# Emoji_Board.net
KiCad netlist of a schematic drawn in EAGLE
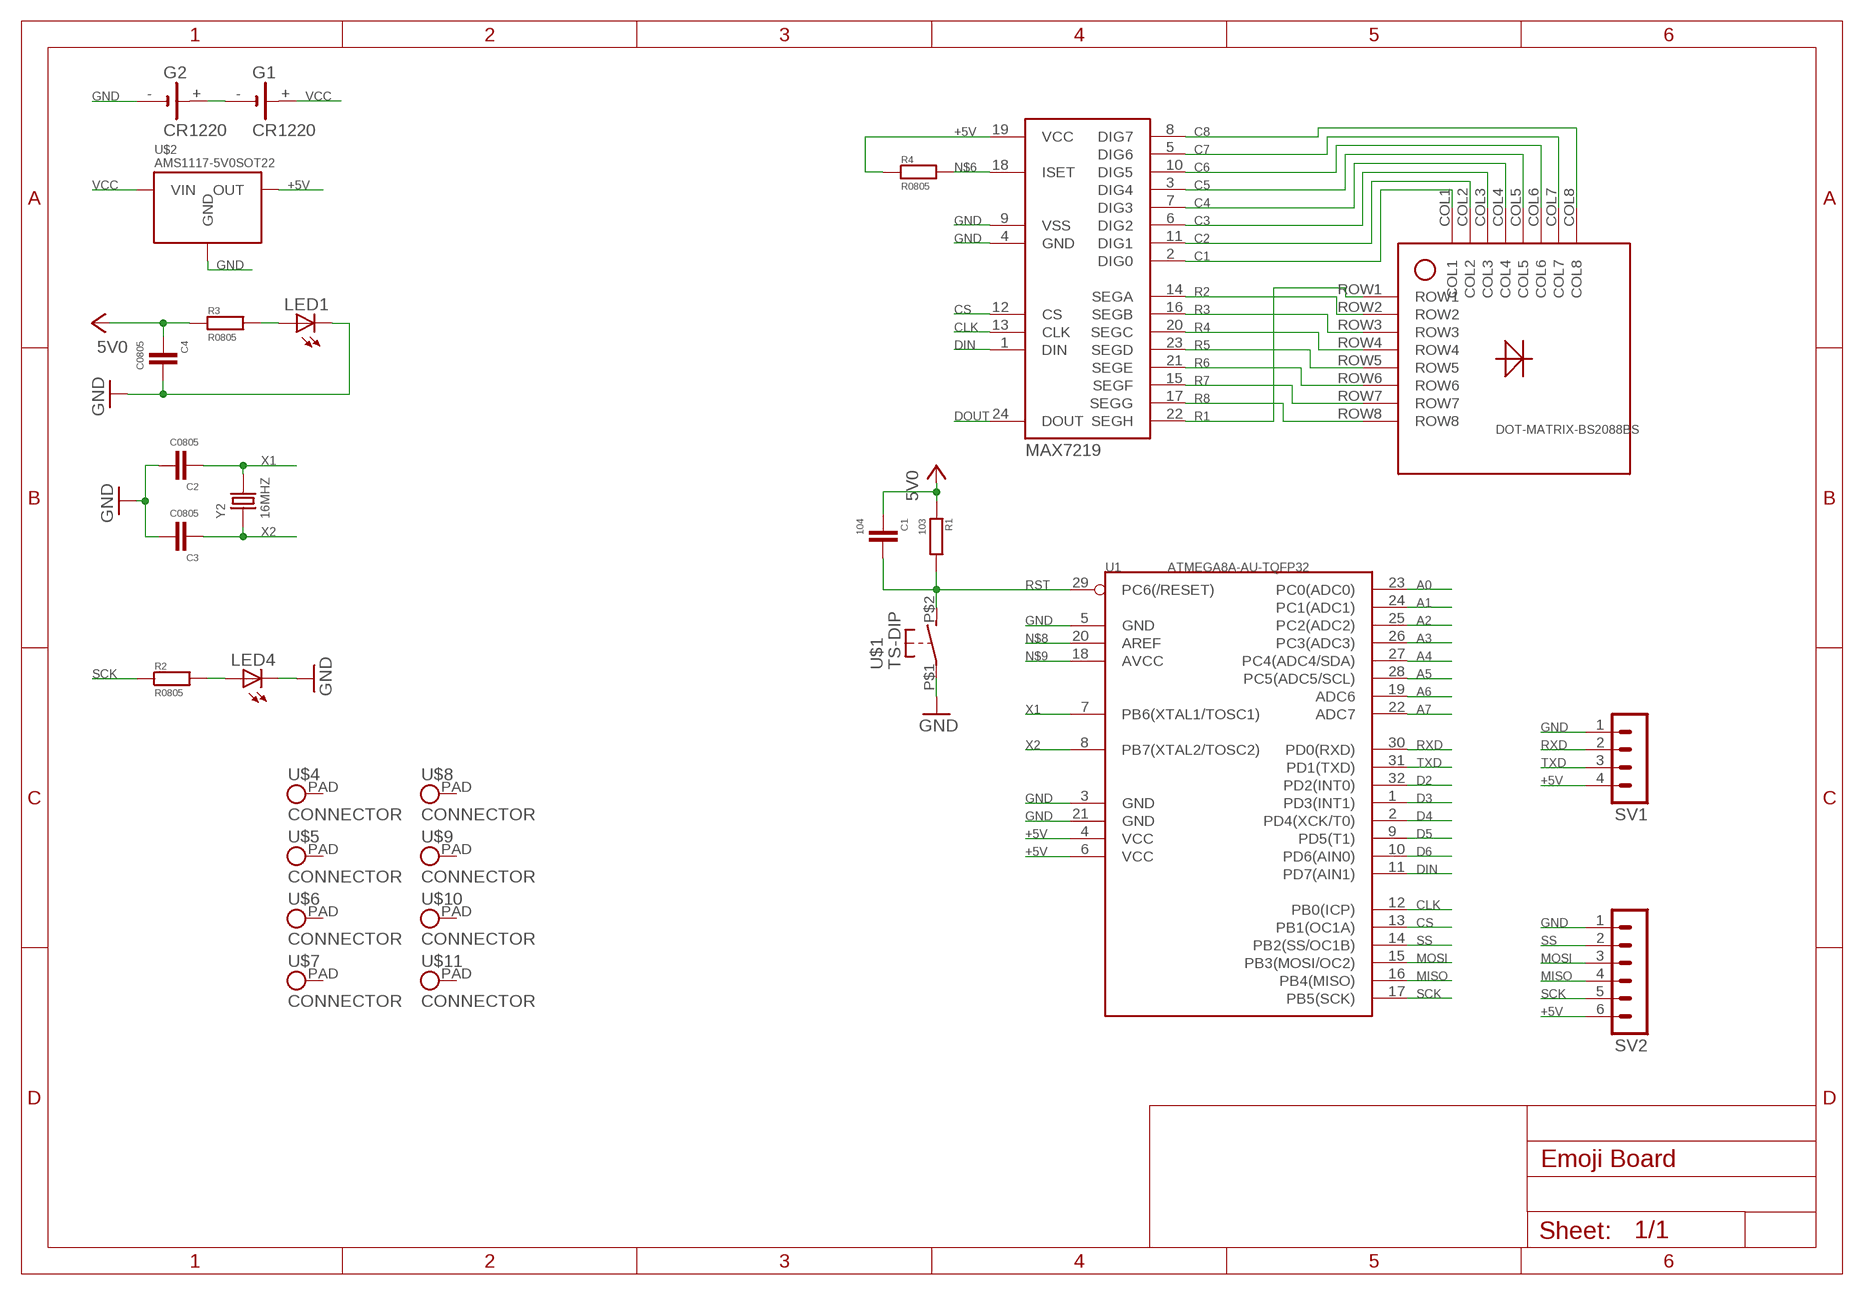
[diagram p0: schematic, sheet 1]

(export (version "E")
  (design (tool "Eeschema 10.0.6"))
  (components
    (comp (ref "C1")
      (value "104")
      (footprint "eagle-import:C0805")
      (libsource (lib "eagle-import") (part "C0805"))
    )
    (comp (ref "C2")
      (value "C0805")
      (footprint "eagle-import:C0805")
      (libsource (lib "eagle-import") (part "C0805"))
    )
    (comp (ref "C3")
      (value "C0805")
      (footprint "eagle-import:C0805")
      (libsource (lib "eagle-import") (part "C0805"))
    )
    (comp (ref "C4")
      (value "C0805")
      (footprint "eagle-import:C0805")
      (libsource (lib "eagle-import") (part "C0805"))
    )
    (comp (ref "G1")
      (value "CR1220")
      (footprint "eagle-import:CR1220")
      (libsource (lib "eagle-import") (part "CR1220"))
    )
    (comp (ref "G2")
      (value "CR1220")
      (footprint "eagle-import:CR1220")
      (libsource (lib "eagle-import") (part "CR1220"))
    )
    (comp (ref "LED1")
      (value "LEDSML0805")
      (footprint "eagle-import:SML0805")
      (libsource (lib "eagle-import") (part "LEDSML0805"))
    )
    (comp (ref "LED4")
      (value "LEDSML0805")
      (footprint "eagle-import:SML0805")
      (libsource (lib "eagle-import") (part "LEDSML0805"))
    )
    (comp (ref "R1")
      (value "103")
      (footprint "eagle-import:R0805")
      (libsource (lib "eagle-import") (part "R0805"))
    )
    (comp (ref "R2")
      (value "R0805")
      (footprint "eagle-import:R0805")
      (libsource (lib "eagle-import") (part "R0805"))
    )
    (comp (ref "R3")
      (value "R0805")
      (footprint "eagle-import:R0805")
      (libsource (lib "eagle-import") (part "R0805"))
    )
    (comp (ref "R4")
      (value "R0805")
      (footprint "eagle-import:R0805")
      (libsource (lib "eagle-import") (part "R0805"))
    )
    (comp (ref "SV1")
      (value "MA04-1")
      (footprint "eagle-import:MA04-1")
      (libsource (lib "eagle-import") (part "MA04-1"))
    )
    (comp (ref "SV2")
      (value "MA06-1")
      (footprint "eagle-import:MA06-1")
      (libsource (lib "eagle-import") (part "MA06-1"))
    )
    (comp (ref "U$1")
      (value "TS-DIP")
      (footprint "eagle-import:TS-DIP")
      (libsource (lib "eagle-import") (part "TS-DIP"))
    )
    (comp (ref "U$2")
      (value "AMS1117-5V0SOT22")
      (footprint "eagle-import:SOT223")
      (libsource (lib "eagle-import") (part "AMS1117-5V0SOT22"))
    )
    (comp (ref "U$3")
      (value "DOT-MATRIX-BS2088BS")
      (footprint "eagle-import:2088BS")
      (libsource (lib "eagle-import") (part "DOT-MATRIX-BS2088BS"))
    )
    (comp (ref "U$4")
      (value "CONNECTOR")
      (footprint "eagle-import:PAD")
      (libsource (lib "eagle-import") (part "CONNECTOR"))
    )
    (comp (ref "U$5")
      (value "CONNECTOR")
      (footprint "eagle-import:PAD")
      (libsource (lib "eagle-import") (part "CONNECTOR"))
    )
    (comp (ref "U$6")
      (value "CONNECTOR")
      (footprint "eagle-import:PAD")
      (libsource (lib "eagle-import") (part "CONNECTOR"))
    )
    (comp (ref "U$7")
      (value "CONNECTOR")
      (footprint "eagle-import:PAD")
      (libsource (lib "eagle-import") (part "CONNECTOR"))
    )
    (comp (ref "U$8")
      (value "CONNECTOR")
      (footprint "eagle-import:PAD")
      (libsource (lib "eagle-import") (part "CONNECTOR"))
    )
    (comp (ref "U$9")
      (value "CONNECTOR")
      (footprint "eagle-import:PAD")
      (libsource (lib "eagle-import") (part "CONNECTOR"))
    )
    (comp (ref "U$10")
      (value "CONNECTOR")
      (footprint "eagle-import:PAD")
      (libsource (lib "eagle-import") (part "CONNECTOR"))
    )
    (comp (ref "U$11")
      (value "CONNECTOR")
      (footprint "eagle-import:PAD")
      (libsource (lib "eagle-import") (part "CONNECTOR"))
    )
    (comp (ref "U$12")
      (value "MAX7219")
      (footprint "eagle-import:SOP24")
      (libsource (lib "eagle-import") (part "MAX7219"))
    )
    (comp (ref "U1")
      (value "ATMEGA8A-AU-TQFP32")
      (footprint "eagle-import:TQFP32")
      (fields (field (name "MPN") "ATMEGA8A-AU"))
      (libsource (lib "eagle-import") (part "ATMEGA8A-AU"))
    )
    (comp (ref "Y2")
      (value "16MHZ")
      (footprint "eagle-import:HC49US")
      (fields (field (name "MPN") "HC-49US    16.000MHz"))
      (libsource (lib "eagle-import") (part "DIP-CRYSTAL-16MHZ-18PF-30PPM-40R(HC49US)"))
    )
  )
  (nets
    (net (code "1") (name "/A0") (class "Default")
      (node (ref "U1") (pin "23") (pinfunction "PC0(ADC0)_23") (pintype "bidirectional"))
    )
    (net (code "2") (name "/A1") (class "Default")
      (node (ref "U1") (pin "24") (pinfunction "PC1(ADC1)_24") (pintype "bidirectional"))
    )
    (net (code "3") (name "/A2") (class "Default")
      (node (ref "U1") (pin "25") (pinfunction "PC2(ADC2)_25") (pintype "bidirectional"))
    )
    (net (code "4") (name "/A3") (class "Default")
      (node (ref "U1") (pin "26") (pinfunction "PC3(ADC3)_26") (pintype "bidirectional"))
    )
    (net (code "5") (name "/A4") (class "Default")
      (node (ref "U1") (pin "27") (pinfunction "PC4(ADC4/SDA)_27") (pintype "bidirectional"))
    )
    (net (code "6") (name "/A5") (class "Default")
      (node (ref "U1") (pin "28") (pinfunction "PC5(ADC5/SCL)_28") (pintype "bidirectional"))
    )
    (net (code "7") (name "/A6") (class "Default")
      (node (ref "U1") (pin "19") (pinfunction "ADC6_19") (pintype "bidirectional"))
    )
    (net (code "8") (name "/A7") (class "Default")
      (node (ref "U1") (pin "22") (pinfunction "ADC7_22") (pintype "bidirectional"))
    )
    (net (code "9") (name "/C1") (class "Default")
      (node (ref "U$12") (pin "2") (pinfunction "DIG0_2") (pintype "input"))
      (node (ref "U$3") (pin "COL1") (pinfunction "COL1_COL1") (pintype "bidirectional"))
    )
    (net (code "10") (name "/C2") (class "Default")
      (node (ref "U$12") (pin "11") (pinfunction "DIG1_11") (pintype "input"))
      (node (ref "U$3") (pin "COL2") (pinfunction "COL2_COL2") (pintype "bidirectional"))
    )
    (net (code "11") (name "/C3") (class "Default")
      (node (ref "U$12") (pin "6") (pinfunction "DIG2_6") (pintype "input"))
      (node (ref "U$3") (pin "COL3") (pinfunction "COL3_COL3") (pintype "bidirectional"))
    )
    (net (code "12") (name "/C4") (class "Default")
      (node (ref "U$12") (pin "7") (pinfunction "DIG3_7") (pintype "input"))
      (node (ref "U$3") (pin "COL4") (pinfunction "COL4_COL4") (pintype "bidirectional"))
    )
    (net (code "13") (name "/C5") (class "Default")
      (node (ref "U$12") (pin "3") (pinfunction "DIG4_3") (pintype "input"))
      (node (ref "U$3") (pin "COL5") (pinfunction "COL5_COL5") (pintype "bidirectional"))
    )
    (net (code "14") (name "/C6") (class "Default")
      (node (ref "U$12") (pin "10") (pinfunction "DIG5_10") (pintype "input"))
      (node (ref "U$3") (pin "COL6") (pinfunction "COL6_COL6") (pintype "bidirectional"))
    )
    (net (code "15") (name "/C7") (class "Default")
      (node (ref "U$12") (pin "5") (pinfunction "DIG6_5") (pintype "input"))
      (node (ref "U$3") (pin "COL7") (pinfunction "COL7_COL7") (pintype "bidirectional"))
    )
    (net (code "16") (name "/C8") (class "Default")
      (node (ref "U$12") (pin "8") (pinfunction "DIG7_8") (pintype "input"))
      (node (ref "U$3") (pin "COL8") (pinfunction "COL8_COL8") (pintype "bidirectional"))
    )
    (net (code "17") (name "/CLK") (class "Default")
      (node (ref "U$12") (pin "13") (pinfunction "CLK_13") (pintype "input"))
      (node (ref "U1") (pin "12") (pinfunction "PB0(ICP)_12") (pintype "bidirectional"))
    )
    (net (code "18") (name "/CS") (class "Default")
      (node (ref "U$12") (pin "12") (pinfunction "CS_12") (pintype "input"))
      (node (ref "U1") (pin "13") (pinfunction "PB1(OC1A)_13") (pintype "bidirectional"))
    )
    (net (code "19") (name "/D2") (class "Default")
      (node (ref "U1") (pin "32") (pinfunction "PD2(INT0)_32") (pintype "bidirectional"))
    )
    (net (code "20") (name "/D3") (class "Default")
      (node (ref "U1") (pin "1") (pinfunction "PD3(INT1)_1") (pintype "bidirectional"))
    )
    (net (code "21") (name "/D4") (class "Default")
      (node (ref "U1") (pin "2") (pinfunction "PD4(XCK/T0)_2") (pintype "bidirectional"))
    )
    (net (code "22") (name "/D5") (class "Default")
      (node (ref "U1") (pin "9") (pinfunction "PD5(T1)_9") (pintype "bidirectional"))
    )
    (net (code "23") (name "/D6") (class "Default")
      (node (ref "U1") (pin "10") (pinfunction "PD6(AIN0)_10") (pintype "bidirectional"))
    )
    (net (code "24") (name "/DIN") (class "Default")
      (node (ref "U$12") (pin "1") (pinfunction "DIN_1") (pintype "input"))
      (node (ref "U1") (pin "11") (pinfunction "PD7(AIN1)_11") (pintype "bidirectional"))
    )
    (net (code "25") (name "/DOUT") (class "Default")
      (node (ref "U$12") (pin "24") (pinfunction "DOUT_24") (pintype "input"))
    )
    (net (code "26") (name "/MISO") (class "Default")
      (node (ref "SV2") (pin "4") (pinfunction "4_4") (pintype "passive"))
      (node (ref "U1") (pin "16") (pinfunction "PB4(MISO)_16") (pintype "bidirectional"))
    )
    (net (code "27") (name "/MOSI") (class "Default")
      (node (ref "SV2") (pin "3") (pinfunction "3_3") (pintype "passive"))
      (node (ref "U1") (pin "15") (pinfunction "PB3(MOSI/OC2)_15") (pintype "bidirectional"))
    )
    (net (code "28") (name "/N$6") (class "Default")
      (node (ref "R4") (pin "2") (pinfunction "2_2") (pintype "bidirectional"))
      (node (ref "U$12") (pin "18") (pinfunction "ISET_18") (pintype "input"))
    )
    (net (code "29") (name "/N$8") (class "Default")
      (node (ref "U1") (pin "20") (pinfunction "AREF_20") (pintype "bidirectional"))
    )
    (net (code "30") (name "/N$9") (class "Default")
      (node (ref "U1") (pin "18") (pinfunction "AVCC_18") (pintype "bidirectional"))
    )
    (net (code "31") (name "/R1") (class "Default")
      (node (ref "U$12") (pin "22") (pinfunction "SEGH_22") (pintype "input"))
      (node (ref "U$3") (pin "ROW1") (pinfunction "ROW1_ROW1") (pintype "bidirectional"))
    )
    (net (code "32") (name "/R2") (class "Default")
      (node (ref "U$12") (pin "14") (pinfunction "SEGA_14") (pintype "input"))
      (node (ref "U$3") (pin "ROW2") (pinfunction "ROW2_ROW2") (pintype "bidirectional"))
    )
    (net (code "33") (name "/R3") (class "Default")
      (node (ref "U$12") (pin "16") (pinfunction "SEGB_16") (pintype "input"))
      (node (ref "U$3") (pin "ROW3") (pinfunction "ROW3_ROW3") (pintype "bidirectional"))
    )
    (net (code "34") (name "/R4") (class "Default")
      (node (ref "U$12") (pin "20") (pinfunction "SEGC_20") (pintype "input"))
      (node (ref "U$3") (pin "ROW4") (pinfunction "ROW4_ROW4") (pintype "bidirectional"))
    )
    (net (code "35") (name "/R5") (class "Default")
      (node (ref "U$12") (pin "23") (pinfunction "SEGD_23") (pintype "input"))
      (node (ref "U$3") (pin "ROW5") (pinfunction "ROW5_ROW5") (pintype "bidirectional"))
    )
    (net (code "36") (name "/R6") (class "Default")
      (node (ref "U$12") (pin "21") (pinfunction "SEGE_21") (pintype "input"))
      (node (ref "U$3") (pin "ROW6") (pinfunction "ROW6_ROW6") (pintype "bidirectional"))
    )
    (net (code "37") (name "/R7") (class "Default")
      (node (ref "U$12") (pin "15") (pinfunction "SEGF_15") (pintype "input"))
      (node (ref "U$3") (pin "ROW7") (pinfunction "ROW7_ROW7") (pintype "bidirectional"))
    )
    (net (code "38") (name "/R8") (class "Default")
      (node (ref "U$12") (pin "17") (pinfunction "SEGG_17") (pintype "input"))
      (node (ref "U$3") (pin "ROW8") (pinfunction "ROW8_ROW8") (pintype "bidirectional"))
    )
    (net (code "39") (name "/RST") (class "Default")
      (node (ref "C1") (pin "1") (pinfunction "1_1") (pintype "bidirectional"))
      (node (ref "R1") (pin "2") (pinfunction "2_2") (pintype "bidirectional"))
      (node (ref "U$1") (pin "P$2") (pinfunction "S_P$2") (pintype "passive"))
      (node (ref "U1") (pin "29") (pinfunction "PC6(/RESET)_29") (pintype "bidirectional"))
    )
    (net (code "40") (name "/RXD") (class "Default")
      (node (ref "SV1") (pin "2") (pinfunction "2_2") (pintype "passive"))
      (node (ref "U1") (pin "30") (pinfunction "PD0(RXD)_30") (pintype "bidirectional"))
    )
    (net (code "41") (name "/SCK") (class "Default")
      (node (ref "R2") (pin "1") (pinfunction "1_1") (pintype "bidirectional"))
      (node (ref "SV2") (pin "5") (pinfunction "5_5") (pintype "passive"))
      (node (ref "U1") (pin "17") (pinfunction "PB5(SCK)_17") (pintype "bidirectional"))
    )
    (net (code "42") (name "/SS") (class "Default")
      (node (ref "SV2") (pin "2") (pinfunction "2_2") (pintype "passive"))
      (node (ref "U1") (pin "14") (pinfunction "PB2(SS/OC1B)_14") (pintype "bidirectional"))
    )
    (net (code "43") (name "/TXD") (class "Default")
      (node (ref "SV1") (pin "3") (pinfunction "3_3") (pintype "passive"))
      (node (ref "U1") (pin "31") (pinfunction "PD1(TXD)_31") (pintype "bidirectional"))
    )
    (net (code "44") (name "/VCC") (class "Default")
      (node (ref "G1") (pin "+") (pinfunction "+_+") (pintype "passive"))
      (node (ref "U$2") (pin "VIN") (pinfunction "VIN_VIN") (pintype "bidirectional"))
    )
    (net (code "45") (name "/X1") (class "Default")
      (node (ref "C2") (pin "2") (pinfunction "2_2") (pintype "bidirectional"))
      (node (ref "U1") (pin "7") (pinfunction "PB6(XTAL1/TOSC1)_7") (pintype "bidirectional"))
      (node (ref "Y2") (pin "2") (pinfunction "2_2") (pintype "passive"))
    )
    (net (code "46") (name "/X2") (class "Default")
      (node (ref "C3") (pin "2") (pinfunction "2_2") (pintype "bidirectional"))
      (node (ref "U1") (pin "8") (pinfunction "PB7(XTAL2/TOSC2)_8") (pintype "bidirectional"))
      (node (ref "Y2") (pin "1") (pinfunction "1_1") (pintype "passive"))
    )
    (net (code "47") (name "5V0") (class "Default")
      (node (ref "C1") (pin "2") (pinfunction "2_2") (pintype "bidirectional"))
      (node (ref "C4") (pin "2") (pinfunction "2_2") (pintype "bidirectional"))
      (node (ref "R1") (pin "1") (pinfunction "1_1") (pintype "bidirectional"))
      (node (ref "R3") (pin "1") (pinfunction "1_1") (pintype "bidirectional"))
      (node (ref "R4") (pin "1") (pinfunction "1_1") (pintype "bidirectional"))
      (node (ref "SV1") (pin "4") (pinfunction "4_4") (pintype "passive"))
      (node (ref "SV2") (pin "6") (pinfunction "6_6") (pintype "passive"))
      (node (ref "U$12") (pin "19") (pinfunction "VCC_19") (pintype "power_in"))
      (node (ref "U$2") (pin "OUT") (pinfunction "OUT_OUT") (pintype "bidirectional"))
      (node (ref "U1") (pin "4") (pinfunction "VCC_4") (pintype "bidirectional"))
      (node (ref "U1") (pin "6") (pinfunction "VCC_6") (pintype "bidirectional"))
    )
    (net (code "48") (name "GND") (class "Default")
      (node (ref "C2") (pin "1") (pinfunction "1_1") (pintype "bidirectional"))
      (node (ref "C3") (pin "1") (pinfunction "1_1") (pintype "bidirectional"))
      (node (ref "C4") (pin "1") (pinfunction "1_1") (pintype "bidirectional"))
      (node (ref "G2") (pin "-") (pinfunction "-_-") (pintype "passive"))
      (node (ref "LED1") (pin "C") (pinfunction "C_C") (pintype "passive"))
      (node (ref "LED4") (pin "C") (pinfunction "C_C") (pintype "passive"))
      (node (ref "SV1") (pin "1") (pinfunction "1_1") (pintype "passive"))
      (node (ref "SV2") (pin "1") (pinfunction "1_1") (pintype "passive"))
      (node (ref "U$1") (pin "P$1") (pinfunction "P_P$1") (pintype "passive"))
      (node (ref "U$12") (pin "4") (pinfunction "GND_4") (pintype "power_in"))
      (node (ref "U$12") (pin "9") (pinfunction "VSS_9") (pintype "power_in"))
      (node (ref "U$2") (pin "GND") (pinfunction "GND_GND") (pintype "bidirectional"))
      (node (ref "U1") (pin "21") (pinfunction "GND_21") (pintype "bidirectional"))
      (node (ref "U1") (pin "3") (pinfunction "GND_3") (pintype "bidirectional"))
      (node (ref "U1") (pin "5") (pinfunction "GND_5") (pintype "bidirectional"))
    )
    (net (code "49") (name "Net-(G1-Pad-)") (class "Default")
      (node (ref "G1") (pin "-") (pinfunction "-_-") (pintype "passive"))
      (node (ref "G2") (pin "+") (pinfunction "+_+") (pintype "passive"))
    )
    (net (code "50") (name "Net-(LED1-PadA)") (class "Default")
      (node (ref "LED1") (pin "A") (pinfunction "A_A") (pintype "passive"))
      (node (ref "R3") (pin "2") (pinfunction "2_2") (pintype "bidirectional"))
    )
    (net (code "51") (name "Net-(LED4-PadA)") (class "Default")
      (node (ref "LED4") (pin "A") (pinfunction "A_A") (pintype "passive"))
      (node (ref "R2") (pin "2") (pinfunction "2_2") (pintype "bidirectional"))
    )
    (net (code "52") (name "unconnected-(U$4-P$1-PadPAD)") (class "Default")
      (node (ref "U$4") (pin "PAD") (pinfunction "P$1_PAD") (pintype "bidirectional"))
    )
    (net (code "53") (name "unconnected-(U$5-P$1-PadPAD)") (class "Default")
      (node (ref "U$5") (pin "PAD") (pinfunction "P$1_PAD") (pintype "bidirectional"))
    )
    (net (code "54") (name "unconnected-(U$6-P$1-PadPAD)") (class "Default")
      (node (ref "U$6") (pin "PAD") (pinfunction "P$1_PAD") (pintype "bidirectional"))
    )
    (net (code "55") (name "unconnected-(U$7-P$1-PadPAD)") (class "Default")
      (node (ref "U$7") (pin "PAD") (pinfunction "P$1_PAD") (pintype "bidirectional"))
    )
    (net (code "56") (name "unconnected-(U$8-P$1-PadPAD)") (class "Default")
      (node (ref "U$8") (pin "PAD") (pinfunction "P$1_PAD") (pintype "bidirectional"))
    )
    (net (code "57") (name "unconnected-(U$9-P$1-PadPAD)") (class "Default")
      (node (ref "U$9") (pin "PAD") (pinfunction "P$1_PAD") (pintype "bidirectional"))
    )
    (net (code "58") (name "unconnected-(U$10-P$1-PadPAD)") (class "Default")
      (node (ref "U$10") (pin "PAD") (pinfunction "P$1_PAD") (pintype "bidirectional"))
    )
    (net (code "59") (name "unconnected-(U$11-P$1-PadPAD)") (class "Default")
      (node (ref "U$11") (pin "PAD") (pinfunction "P$1_PAD") (pintype "bidirectional"))
    )
  )
)
